# SensorPCB.net
KiCad netlist of a schematic drawn in Altium Designer
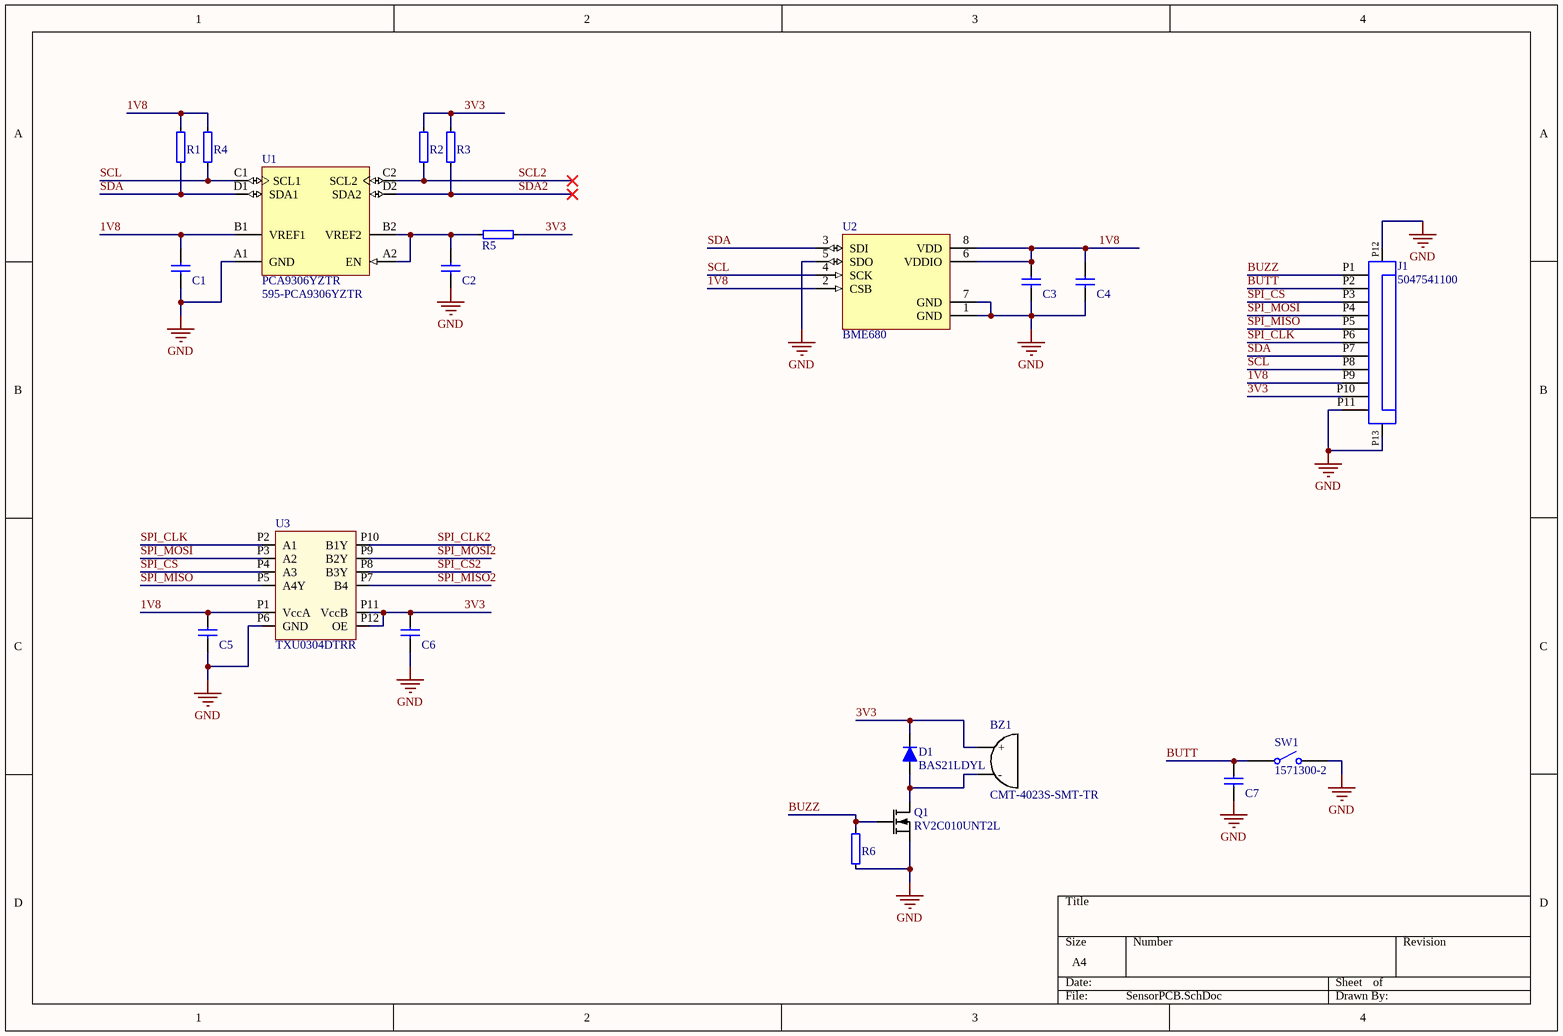
[diagram p0: SensorPCB.SchDoc]

(export (version "E")
  (design (tool "Eeschema 10.0.6"))
  (components
    (comp (ref "BZ1")
      (value "CMT-4023S-SMT-TR")
      (footprint "CMT-4023S-SMT-TR")
      (description "4 mm, 3 Vo-p, 70 dB, Surface Mount (SMT), Magnetic Audio Transducer Buzzer")
      (fields (field (name "MANUFACTURER") "CUI"))
      (libsource (lib "Schlib1") (part "CMT-4023S-SMT-TR"))
    )
    (comp (ref "C1") (value "100n") (footprint "CAPC0603X03L_C") (libsource (lib "Schlib1") (part "C0201")))
    (comp (ref "C2") (value "100n") (footprint "CAPC0603X03L_C") (libsource (lib "Schlib1") (part "C0201")))
    (comp (ref "C3") (value "100n") (footprint "CAPC0603X03L_C") (libsource (lib "Schlib1") (part "C0201")))
    (comp (ref "C4") (value "100n") (footprint "CAPC0603X03L_C") (libsource (lib "Schlib1") (part "C0201")))
    (comp (ref "C5") (value "100n") (footprint "CAPC0603X03L_C") (libsource (lib "Schlib1") (part "C0201")))
    (comp (ref "C6") (value "100n") (footprint "CAPC0603X03L_C") (libsource (lib "Schlib1") (part "C0201")))
    (comp (ref "C7") (value "100n") (footprint "CAPC0603X03L_C") (libsource (lib "Schlib1") (part "C0201")))
    (comp (ref "D1")
      (value "BAS21LDYL")
      (footprint "BAS21LDYL")
      (description "BAS21LD/SOD882/SOD2")
      (fields (field (name "MANUFACTURER") "Nexperia"))
      (libsource (lib "Schlib1") (part "BAS21LDYL"))
    )
    (comp (ref "J1")
      (value "5047541100")
      (footprint "5047541100")
      (description "Conn FFC/FPC Connector SKT 11 POS 0.3mm Solder RA SMD Easy-On™ T/R")
      (fields
        (field (name "MANUFACTURER PART NUMBER") "687124182122")
        (field (name "MANUFACTURER") "Wurth Elektronik")
      )
      (libsource (lib "Schlib1") (part "5047541100"))
    )
    (comp (ref "Q1")
      (value "RV2C010UNT2L")
      (footprint "DFN65P100X40-3L")
      (description "N-Channel MOSFET, 20V, 1A, 470mOhm, 400mW")
      (fields (field (name "MANUFACTURER") "Rohm Semiconductor"))
      (libsource (lib "main") (part "RV2C010UNT2L"))
    )
    (comp (ref "R1") (value "4.7k") (footprint "RESC0603X03L_C") (libsource (lib "Schlib1") (part "R0201")))
    (comp (ref "R2") (value "4.7k") (footprint "RESC0603X03L_C") (libsource (lib "Schlib1") (part "R0201")))
    (comp (ref "R3") (value "4.7k") (footprint "RESC0603X03L_C") (libsource (lib "Schlib1") (part "R0201")))
    (comp (ref "R4") (value "4.7k") (footprint "RESC0603X03L_C") (libsource (lib "Schlib1") (part "R0201")))
    (comp (ref "R5") (value "200k") (footprint "RESC0603X03L_C") (libsource (lib "Schlib1") (part "R0201")))
    (comp (ref "R6") (value "200k") (footprint "RESC0603X03L_C") (libsource (lib "Schlib1") (part "R0201")))
    (comp (ref "SW1")
      (value "1571300-2")
      (footprint "1571300-2")
      (description "Switch Tactile OFF (ON) SPST Round Button Gull Wing 0.05A 12VDC 1.27N SMD Loose Piece")
      (fields (field (name "MANUFACTURER") "TE Connectivity"))
      (libsource (lib "Schlib1") (part "1571300-2"))
    )
    (comp (ref "U1")
      (value "PCA9306YZTR")
      (footprint "PCA9306YZTR")
      (description "PCA9306 2-BIT Bidirectional I2C")
      (fields
        (field (name "MANUFACTURER") "Texas Instruments")
        (field (name "SUPPLIER PART NUMBER 1") "595-PCA9306YZTR")
      )
      (libsource (lib "Schlib1") (part "PCA9306YZTR"))
    )
    (comp (ref "U2")
      (value "BME680")
      (footprint "BME680")
      (description "Low power gas, pressure, temperature & humidity sensor")
      (fields (field (name "MANUFACTURER") "Bosch"))
      (libsource (lib "main") (part "BME680"))
    )
    (comp (ref "U3")
      (value "TXU0304DTRR")
      (footprint "TXU0304DTR")
      (description "Four-channel fixed multidirectional level shifter 12-X2QFN -40 to 125")
      (fields (field (name "MANUFACTURER") "Texas Instruments"))
      (libsource (lib "Schlib1") (part "TXU0304DTRR"))
    )
  )
  (nets
    (net (code "1") (name "/1V8") (class "Default")
      (node (ref "C1") (pin "2") (pinfunction "2_2") (pintype "passive"))
      (node (ref "C3") (pin "2") (pinfunction "2_2") (pintype "passive"))
      (node (ref "C4") (pin "2") (pinfunction "2_2") (pintype "passive"))
      (node (ref "C5") (pin "2") (pinfunction "2_2") (pintype "passive"))
      (node (ref "J1") (pin "P9") (pinfunction "9_P9") (pintype "passive"))
      (node (ref "R1") (pin "2") (pinfunction "2_2") (pintype "passive"))
      (node (ref "R4") (pin "2") (pinfunction "2_2") (pintype "passive"))
      (node (ref "U1") (pin "B1") (pinfunction "VREF1_B1") (pintype "power_in"))
      (node (ref "U2") (pin "2") (pinfunction "CSB_2") (pintype "input"))
      (node (ref "U2") (pin "6") (pinfunction "VDDIO_6") (pintype "power_in"))
      (node (ref "U2") (pin "8") (pinfunction "VDD_8") (pintype "power_in"))
      (node (ref "U3") (pin "P1") (pinfunction "VccA_P1") (pintype "passive"))
    )
    (net (code "2") (name "/3V3") (class "Default")
      (node (ref "BZ1") (pin "P1") (pinfunction "+_P1") (pintype "passive"))
      (node (ref "C6") (pin "2") (pinfunction "2_2") (pintype "passive"))
      (node (ref "D1") (pin "P2") (pinfunction "K_P2") (pintype "passive"))
      (node (ref "J1") (pin "P10") (pinfunction "10_P10") (pintype "passive"))
      (node (ref "R2") (pin "2") (pinfunction "2_2") (pintype "passive"))
      (node (ref "R3") (pin "2") (pinfunction "2_2") (pintype "passive"))
      (node (ref "R5") (pin "1") (pinfunction "1_1") (pintype "passive"))
      (node (ref "U3") (pin "P11") (pinfunction "VccB_P11") (pintype "passive"))
      (node (ref "U3") (pin "P12") (pinfunction "OE_P12") (pintype "passive"))
    )
    (net (code "3") (name "/BUTT") (class "Default")
      (node (ref "C7") (pin "2") (pinfunction "2_2") (pintype "passive"))
      (node (ref "J1") (pin "P2") (pinfunction "2_P2") (pintype "passive"))
      (node (ref "SW1") (pin "P1") (pinfunction "1_P1") (pintype "passive"))
    )
    (net (code "4") (name "/BUZZ") (class "Default")
      (node (ref "J1") (pin "P1") (pinfunction "1_P1") (pintype "passive"))
      (node (ref "Q1") (pin "1") (pinfunction "G_1") (pintype "passive"))
      (node (ref "R6") (pin "1") (pinfunction "1_1") (pintype "passive"))
    )
    (net (code "5") (name "/SCL") (class "Default")
      (node (ref "J1") (pin "P8") (pinfunction "8_P8") (pintype "passive"))
      (node (ref "R4") (pin "1") (pinfunction "1_1") (pintype "passive"))
      (node (ref "U1") (pin "C1") (pinfunction "SCL1_C1") (pintype "bidirectional"))
      (node (ref "U2") (pin "4") (pinfunction "SCK_4") (pintype "input"))
    )
    (net (code "6") (name "/SCL2") (class "Default")
      (node (ref "R2") (pin "1") (pinfunction "1_1") (pintype "passive"))
      (node (ref "U1") (pin "C2") (pinfunction "SCL2_C2") (pintype "bidirectional"))
    )
    (net (code "7") (name "/SDA") (class "Default")
      (node (ref "J1") (pin "P7") (pinfunction "7_P7") (pintype "passive"))
      (node (ref "R1") (pin "1") (pinfunction "1_1") (pintype "passive"))
      (node (ref "U1") (pin "D1") (pinfunction "SDA1_D1") (pintype "bidirectional"))
      (node (ref "U2") (pin "3") (pinfunction "SDI_3") (pintype "bidirectional"))
    )
    (net (code "8") (name "/SDA2") (class "Default")
      (node (ref "R3") (pin "1") (pinfunction "1_1") (pintype "passive"))
      (node (ref "U1") (pin "D2") (pinfunction "SDA2_D2") (pintype "bidirectional"))
    )
    (net (code "9") (name "/SPI_CLK") (class "Default")
      (node (ref "J1") (pin "P6") (pinfunction "6_P6") (pintype "passive"))
      (node (ref "U3") (pin "P2") (pinfunction "A1_P2") (pintype "passive"))
    )
    (net (code "10") (name "/SPI_CLK2") (class "Default")
      (node (ref "U3") (pin "P10") (pinfunction "B1Y_P10") (pintype "passive"))
    )
    (net (code "11") (name "/SPI_CS") (class "Default")
      (node (ref "J1") (pin "P3") (pinfunction "3_P3") (pintype "passive"))
      (node (ref "U3") (pin "P4") (pinfunction "A3_P4") (pintype "passive"))
    )
    (net (code "12") (name "/SPI_CS2") (class "Default")
      (node (ref "U3") (pin "P8") (pinfunction "B3Y_P8") (pintype "passive"))
    )
    (net (code "13") (name "/SPI_MISO") (class "Default")
      (node (ref "J1") (pin "P5") (pinfunction "5_P5") (pintype "passive"))
      (node (ref "U3") (pin "P5") (pinfunction "A4Y_P5") (pintype "passive"))
    )
    (net (code "14") (name "/SPI_MISO2") (class "Default")
      (node (ref "U3") (pin "P7") (pinfunction "B4_P7") (pintype "passive"))
    )
    (net (code "15") (name "/SPI_MOSI") (class "Default")
      (node (ref "J1") (pin "P4") (pinfunction "4_P4") (pintype "passive"))
      (node (ref "U3") (pin "P3") (pinfunction "A2_P3") (pintype "passive"))
    )
    (net (code "16") (name "/SPI_MOSI2") (class "Default")
      (node (ref "U3") (pin "P9") (pinfunction "B2Y_P9") (pintype "passive"))
    )
    (net (code "17") (name "GND") (class "Default")
      (node (ref "C1") (pin "1") (pinfunction "1_1") (pintype "passive"))
      (node (ref "C2") (pin "1") (pinfunction "1_1") (pintype "passive"))
      (node (ref "C3") (pin "1") (pinfunction "1_1") (pintype "passive"))
      (node (ref "C4") (pin "1") (pinfunction "1_1") (pintype "passive"))
      (node (ref "C5") (pin "1") (pinfunction "1_1") (pintype "passive"))
      (node (ref "C6") (pin "1") (pinfunction "1_1") (pintype "passive"))
      (node (ref "C7") (pin "1") (pinfunction "1_1") (pintype "passive"))
      (node (ref "J1") (pin "P11") (pinfunction "11_P11") (pintype "passive"))
      (node (ref "J1") (pin "P12") (pinfunction "MP1_P12") (pintype "passive"))
      (node (ref "J1") (pin "P13") (pinfunction "MP2_P13") (pintype "passive"))
      (node (ref "Q1") (pin "2") (pinfunction "S_2") (pintype "passive"))
      (node (ref "R6") (pin "2") (pinfunction "2_2") (pintype "passive"))
      (node (ref "SW1") (pin "P2") (pinfunction "2_P2") (pintype "passive"))
      (node (ref "U1") (pin "A1") (pinfunction "GND_A1") (pintype "power_in"))
      (node (ref "U2") (pin "1") (pinfunction "GND_1") (pintype "power_in"))
      (node (ref "U2") (pin "5") (pinfunction "SDO_5") (pintype "bidirectional"))
      (node (ref "U2") (pin "7") (pinfunction "GND_7") (pintype "power_in"))
      (node (ref "U3") (pin "P6") (pinfunction "GND_P6") (pintype "passive"))
    )
    (net (code "18") (name "Net-(BZ1--)") (class "Default")
      (node (ref "BZ1") (pin "P2") (pinfunction "-_P2") (pintype "passive"))
      (node (ref "D1") (pin "P1") (pinfunction "A_P1") (pintype "passive"))
      (node (ref "Q1") (pin "3") (pinfunction "D_3") (pintype "passive"))
    )
    (net (code "19") (name "Net-(U1-EN)") (class "Default")
      (node (ref "C2") (pin "2") (pinfunction "2_2") (pintype "passive"))
      (node (ref "R5") (pin "2") (pinfunction "2_2") (pintype "passive"))
      (node (ref "U1") (pin "A2") (pinfunction "EN_A2") (pintype "input"))
      (node (ref "U1") (pin "B2") (pinfunction "VREF2_B2") (pintype "power_in"))
    )
  )
)
